# Termo_l_nok.net
KiCad netlist of a schematic drawn in Altium Designer
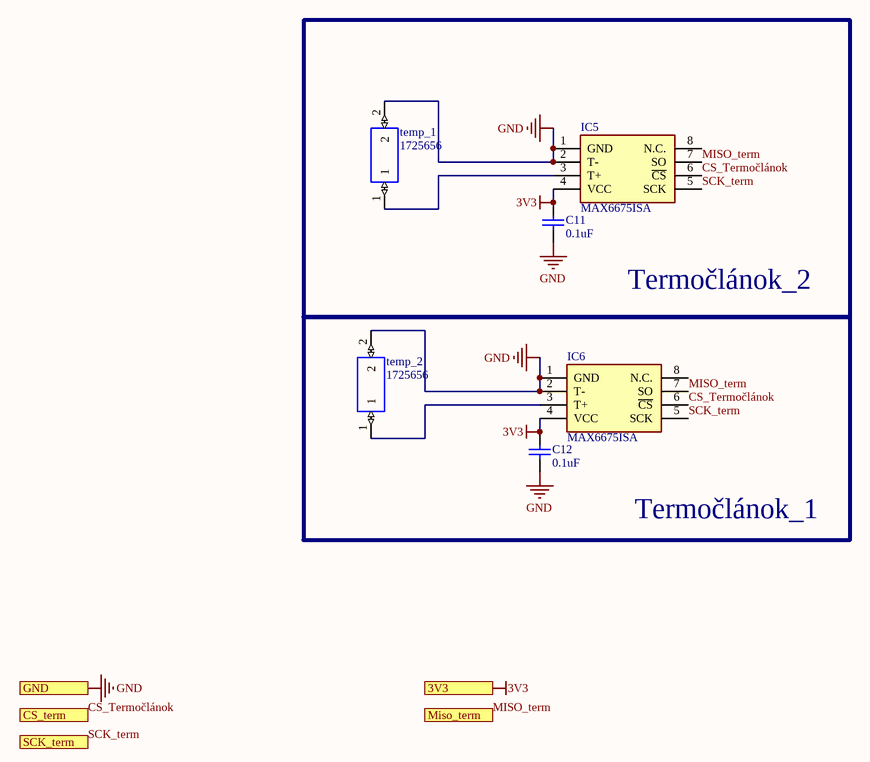
[diagram p0: Termočlánok.SchDoc]

(export (version "E")
  (design (tool "Eeschema 10.0.6"))
  (components
    (comp (ref "C11")
      (value "0.1uF")
      (footprint "1608[0603]")
      (description "Capacitor (Semiconductor SIM Model)")
      (fields (field (name "PUBLISHER") "Altium Limited"))
      (libsource (lib "Miscellaneous Devices") (part "Cap Semi"))
    )
    (comp (ref "C12")
      (value "0.1uF")
      (footprint "1608[0603]")
      (description "Capacitor (Semiconductor SIM Model)")
      (fields (field (name "PUBLISHER") "Altium Limited"))
      (libsource (lib "Miscellaneous Devices") (part "Cap Semi"))
    )
    (comp (ref "IC5")
      (value "MAX6675ISA")
      (footprint "SamacSys:SOIC127P600X175-8N")
      (description "Integrated Circuit")
      (libsource (lib "*") (part "MAX6675ISA"))
    )
    (comp (ref "IC6")
      (value "MAX6675ISA")
      (footprint "SamacSys:SOIC127P600X175-8N")
      (description "Integrated Circuit")
      (libsource (lib "*") (part "MAX6675ISA"))
    )
    (comp (ref "temp_1")
      (value "1725656")
      (footprint "1725656")
      (description "2 way PCB vertical mount terminal,2.54mm 2 way PCB vertical mount terminal,2.54mm")
      (fields (field (name "RS PART NUMBER") "2204260"))
      (libsource (lib "1725656") (part "1725656"))
    )
    (comp (ref "temp_2")
      (value "1725656")
      (footprint "1725656")
      (description "2 way PCB vertical mount terminal,2.54mm 2 way PCB vertical mount terminal,2.54mm")
      (fields (field (name "RS PART NUMBER") "2204260"))
      (libsource (lib "1725656") (part "1725656"))
    )
  )
  (nets
    (net (code "1") (name "/CS_Termočlánok") (class "Default")
      (node (ref "IC5") (pin "6") (pinfunction "~{CS}_6") (pintype "passive"))
      (node (ref "IC6") (pin "6") (pinfunction "~{CS}_6") (pintype "passive"))
    )
    (net (code "2") (name "/MISO_term") (class "Default")
      (node (ref "IC5") (pin "7") (pinfunction "SO_7") (pintype "passive"))
      (node (ref "IC6") (pin "7") (pinfunction "SO_7") (pintype "passive"))
    )
    (net (code "3") (name "/SCK_term") (class "Default")
      (node (ref "IC5") (pin "5") (pinfunction "SCK_5") (pintype "passive"))
      (node (ref "IC6") (pin "5") (pinfunction "SCK_5") (pintype "passive"))
    )
    (net (code "4") (name "3V3") (class "Default")
      (node (ref "C11") (pin "2") (pinfunction "2_2") (pintype "passive"))
      (node (ref "C12") (pin "2") (pinfunction "2_2") (pintype "passive"))
      (node (ref "IC5") (pin "4") (pinfunction "VCC_4") (pintype "passive"))
      (node (ref "IC6") (pin "4") (pinfunction "VCC_4") (pintype "passive"))
    )
    (net (code "5") (name "GND") (class "Default")
      (node (ref "C11") (pin "1") (pinfunction "1_1") (pintype "passive"))
      (node (ref "C12") (pin "1") (pinfunction "1_1") (pintype "passive"))
      (node (ref "IC5") (pin "1") (pinfunction "GND_1") (pintype "passive"))
      (node (ref "IC5") (pin "2") (pinfunction "T-_2") (pintype "passive"))
      (node (ref "IC6") (pin "1") (pinfunction "GND_1") (pintype "passive"))
      (node (ref "IC6") (pin "2") (pinfunction "T-_2") (pintype "passive"))
      (node (ref "temp_1") (pin "2") (pinfunction "2_2") (pintype "bidirectional"))
      (node (ref "temp_2") (pin "2") (pinfunction "2_2") (pintype "bidirectional"))
    )
    (net (code "6") (name "Net-(IC5-T+)") (class "Default")
      (node (ref "IC5") (pin "3") (pinfunction "T+_3") (pintype "passive"))
      (node (ref "temp_1") (pin "1") (pinfunction "1_1") (pintype "bidirectional"))
    )
    (net (code "7") (name "Net-(IC6-T+)") (class "Default")
      (node (ref "IC6") (pin "3") (pinfunction "T+_3") (pintype "passive"))
      (node (ref "temp_2") (pin "1") (pinfunction "1_1") (pintype "bidirectional"))
    )
    (net (code "8") (name "unconnected-(IC5-N.C.-Pad8)") (class "Default")
      (node (ref "IC5") (pin "8") (pinfunction "N.C._8") (pintype "passive"))
    )
    (net (code "9") (name "unconnected-(IC6-N.C.-Pad8)") (class "Default")
      (node (ref "IC6") (pin "8") (pinfunction "N.C._8") (pintype "passive"))
    )
  )
)
